# Sheet1.net
KiCad netlist of a schematic drawn in Altium Designer
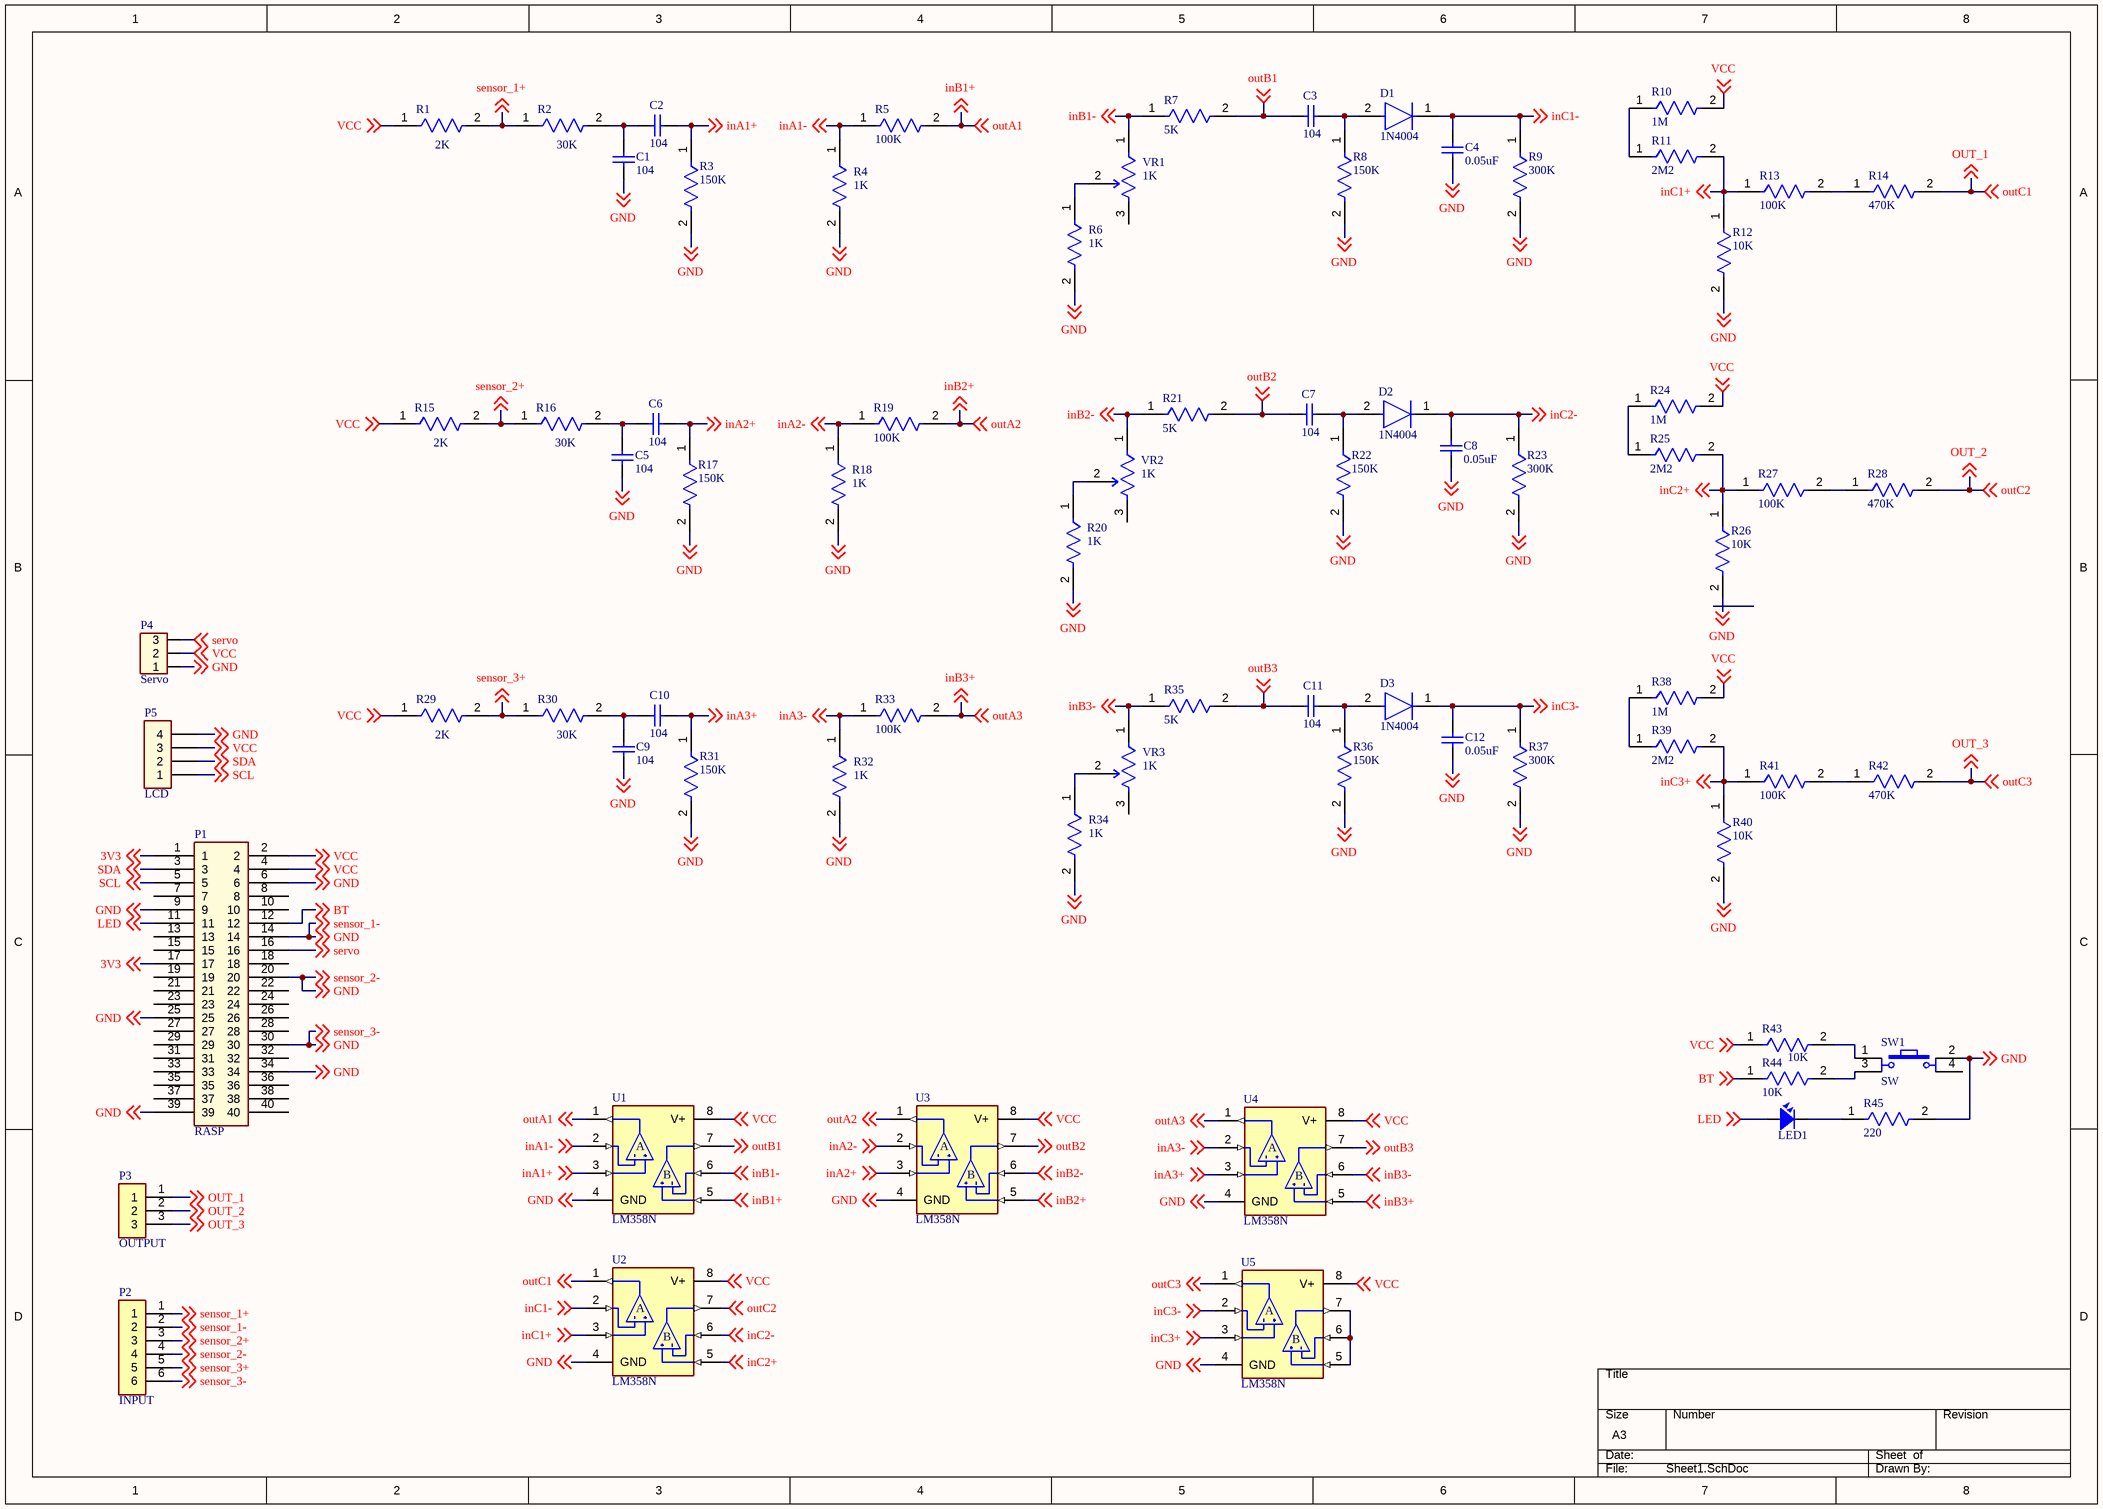
[diagram p0: Sheet1.SchDoc]

(export (version "E")
  (design (tool "Eeschema 10.0.6"))
  (components
    (comp (ref "C1")
      (value "104")
      (footprint "CAP_CERAMIC_MULTI")
      (description "Radial Multilayer Ceramic Capacitor")
      (fields
        (field (name "MANUFACTURER") "Kyocera AVX")
        (field (name "MANUFACTURER PART NUMBER") "LD051C104KAB2A")
      )
      (libsource (lib "Lib_BookTS") (part "CAP RADIAL"))
    )
    (comp (ref "C2")
      (value "104")
      (footprint "CAP_CERAMIC_MULTI")
      (description "Radial Multilayer Ceramic Capacitor")
      (fields
        (field (name "MANUFACTURER") "Kyocera AVX")
        (field (name "MANUFACTURER PART NUMBER") "LD051C104KAB2A")
      )
      (libsource (lib "Lib_BookTS") (part "CAP RADIAL"))
    )
    (comp (ref "C3")
      (value "104")
      (footprint "CAP_CERAMIC_MULTI")
      (description "Radial Multilayer Ceramic Capacitor")
      (fields
        (field (name "MANUFACTURER") "Kyocera AVX")
        (field (name "MANUFACTURER PART NUMBER") "LD051C104KAB2A")
      )
      (libsource (lib "Lib_BookTS") (part "CAP RADIAL"))
    )
    (comp (ref "C4")
      (value "0.05uF")
      (footprint "CAP_CERAMIC_MULTI")
      (description "Radial Multilayer Ceramic Capacitor")
      (fields
        (field (name "MANUFACTURER") "Kyocera AVX")
        (field (name "MANUFACTURER PART NUMBER") "LD051C104KAB2A")
      )
      (libsource (lib "Lib_BookTS") (part "CAP RADIAL"))
    )
    (comp (ref "C5")
      (value "104")
      (footprint "CAP_CERAMIC_MULTI")
      (description "Radial Multilayer Ceramic Capacitor")
      (fields
        (field (name "MANUFACTURER") "Kyocera AVX")
        (field (name "MANUFACTURER PART NUMBER") "LD051C104KAB2A")
      )
      (libsource (lib "Lib_BookTS") (part "CAP RADIAL"))
    )
    (comp (ref "C6")
      (value "104")
      (footprint "CAP_CERAMIC_MULTI")
      (description "Radial Multilayer Ceramic Capacitor")
      (fields
        (field (name "MANUFACTURER") "Kyocera AVX")
        (field (name "MANUFACTURER PART NUMBER") "LD051C104KAB2A")
      )
      (libsource (lib "Lib_BookTS") (part "CAP RADIAL"))
    )
    (comp (ref "C7")
      (value "104")
      (footprint "CAP_CERAMIC_MULTI")
      (description "Radial Multilayer Ceramic Capacitor")
      (fields
        (field (name "MANUFACTURER") "Kyocera AVX")
        (field (name "MANUFACTURER PART NUMBER") "LD051C104KAB2A")
      )
      (libsource (lib "Lib_BookTS") (part "CAP RADIAL"))
    )
    (comp (ref "C8")
      (value "0.05uF")
      (footprint "CAP_CERAMIC_MULTI")
      (description "Radial Multilayer Ceramic Capacitor")
      (fields
        (field (name "MANUFACTURER") "Kyocera AVX")
        (field (name "MANUFACTURER PART NUMBER") "LD051C104KAB2A")
      )
      (libsource (lib "Lib_BookTS") (part "CAP RADIAL"))
    )
    (comp (ref "C9")
      (value "104")
      (footprint "CAP_CERAMIC_MULTI")
      (description "Radial Multilayer Ceramic Capacitor")
      (fields
        (field (name "MANUFACTURER") "Kyocera AVX")
        (field (name "MANUFACTURER PART NUMBER") "LD051C104KAB2A")
      )
      (libsource (lib "Lib_BookTS") (part "CAP RADIAL"))
    )
    (comp (ref "C10")
      (value "104")
      (footprint "CAP_CERAMIC_MULTI")
      (description "Radial Multilayer Ceramic Capacitor")
      (fields
        (field (name "MANUFACTURER") "Kyocera AVX")
        (field (name "MANUFACTURER PART NUMBER") "LD051C104KAB2A")
      )
      (libsource (lib "Lib_BookTS") (part "CAP RADIAL"))
    )
    (comp (ref "C11")
      (value "104")
      (footprint "CAP_CERAMIC_MULTI")
      (description "Radial Multilayer Ceramic Capacitor")
      (fields
        (field (name "MANUFACTURER") "Kyocera AVX")
        (field (name "MANUFACTURER PART NUMBER") "LD051C104KAB2A")
      )
      (libsource (lib "Lib_BookTS") (part "CAP RADIAL"))
    )
    (comp (ref "C12")
      (value "0.05uF")
      (footprint "CAP_CERAMIC_MULTI")
      (description "Radial Multilayer Ceramic Capacitor")
      (fields
        (field (name "MANUFACTURER") "Kyocera AVX")
        (field (name "MANUFACTURER PART NUMBER") "LD051C104KAB2A")
      )
      (libsource (lib "Lib_BookTS") (part "CAP RADIAL"))
    )
    (comp (ref "D1")
      (value "1N4004")
      (footprint "DO-41")
      (description "Diode 1N4004 DO-41, 400V, 1.00A")
      (fields (field (name "MANUFACTURER") "Diotec") (field (name "MANUFACTURER PART NUMBER") "1N4007"))
      (libsource (lib "Lib_BookTS") (part "1N4004"))
    )
    (comp (ref "D2")
      (value "1N4004")
      (footprint "DO-41")
      (description "Diode 1N4004 DO-41, 400V, 1.00A")
      (fields (field (name "MANUFACTURER") "Diotec") (field (name "MANUFACTURER PART NUMBER") "1N4007"))
      (libsource (lib "Lib_BookTS") (part "1N4004"))
    )
    (comp (ref "D3")
      (value "1N4004")
      (footprint "DO-41")
      (description "Diode 1N4004 DO-41, 400V, 1.00A")
      (fields (field (name "MANUFACTURER") "Diotec") (field (name "MANUFACTURER PART NUMBER") "1N4007"))
      (libsource (lib "Lib_BookTS") (part "1N4004"))
    )
    (comp (ref "LED1")
      (value "LED")
      (footprint "LED-5-BLUE")
      (description "LED Single colour Green and Red")
      (libsource (lib "Lib_BookTS") (part "LED"))
    )
    (comp (ref "P1")
      (value "RASP")
      (footprint "HED20X2")
      (description "HEADER 2X20P")
      (fields (field (name "MANUFACTURER") "Harwin") (field (name "MANUFACTURER PART NUMBER") "M20-9990246"))
      (libsource (lib "Lib_BookTS") (part "HEADER 2X20P"))
    )
    (comp (ref "P2")
      (value "INPUT")
      (footprint "JP6")
      (fields (field (name "MANUFACTURER") "Harwin") (field (name "MANUFACTURER PART NUMBER") "M20-9990246"))
      (libsource (lib "Lib_BookTS") (part "JP6"))
    )
    (comp (ref "P3")
      (value "OUTPUT")
      (footprint "JP3")
      (description "HEADER 3P")
      (fields (field (name "MANUFACTURER") "Harwin") (field (name "MANUFACTURER PART NUMBER") "M20-9990246"))
      (libsource (lib "Lib_BookTS") (part "JP3"))
    )
    (comp (ref "P4")
      (value "Servo")
      (footprint "CON3")
      (description "Connector 3")
      (libsource (lib "Lib_BookTS") (part "Con3"))
    )
    (comp (ref "P5")
      (value "LCD")
      (footprint "CON4")
      (description "Connector 4")
      (libsource (lib "Lib_BookTS") (part "CON 4"))
    )
    (comp (ref "R1")
      (value "2K")
      (footprint "RES-1/8W-SMALL")
      (description "RES 1/8W")
      (fields
        (field (name "MANUFACTURER") "Bourns")
        (field (name "MANUFACTURER PART NUMBER") "CR0805-JW-331ELF")
      )
      (libsource (lib "Lib_BookTS") (part "RES-1/8W"))
    )
    (comp (ref "R2")
      (value "30K")
      (footprint "RES-1/8W-SMALL")
      (description "RES 1/8W")
      (fields
        (field (name "MANUFACTURER") "Bourns")
        (field (name "MANUFACTURER PART NUMBER") "CR0805-JW-331ELF")
      )
      (libsource (lib "Lib_BookTS") (part "RES-1/8W"))
    )
    (comp (ref "R3")
      (value "150K")
      (footprint "RES-1/8W-SMALL")
      (description "RES 1/8W")
      (fields
        (field (name "MANUFACTURER") "Bourns")
        (field (name "MANUFACTURER PART NUMBER") "CR0805-JW-331ELF")
      )
      (libsource (lib "Lib_BookTS") (part "RES-1/8W"))
    )
    (comp (ref "R4")
      (value "1K")
      (footprint "RES-1/8W-SMALL")
      (description "RES 1/8W")
      (fields
        (field (name "MANUFACTURER") "Bourns")
        (field (name "MANUFACTURER PART NUMBER") "CR0805-JW-331ELF")
      )
      (libsource (lib "Lib_BookTS") (part "RES-1/8W"))
    )
    (comp (ref "R5")
      (value "100K")
      (footprint "RES-1/8W-SMALL")
      (description "RES 1/8W")
      (fields
        (field (name "MANUFACTURER") "Bourns")
        (field (name "MANUFACTURER PART NUMBER") "CR0805-JW-331ELF")
      )
      (libsource (lib "Lib_BookTS") (part "RES-1/8W"))
    )
    (comp (ref "R6")
      (value "1K")
      (footprint "RES-1/8W-SMALL")
      (description "RES 1/8W")
      (fields
        (field (name "MANUFACTURER") "Bourns")
        (field (name "MANUFACTURER PART NUMBER") "CR0805-JW-331ELF")
      )
      (libsource (lib "Lib_BookTS") (part "RES-1/8W"))
    )
    (comp (ref "R7")
      (value "5K")
      (footprint "RES-1/8W-SMALL")
      (description "RES 1/8W")
      (fields
        (field (name "MANUFACTURER") "Bourns")
        (field (name "MANUFACTURER PART NUMBER") "CR0805-JW-331ELF")
      )
      (libsource (lib "Lib_BookTS") (part "RES-1/8W"))
    )
    (comp (ref "R8")
      (value "150K")
      (footprint "RES-1/8W-SMALL")
      (description "RES 1/8W")
      (fields
        (field (name "MANUFACTURER") "Bourns")
        (field (name "MANUFACTURER PART NUMBER") "CR0805-JW-331ELF")
      )
      (libsource (lib "Lib_BookTS") (part "RES-1/8W"))
    )
    (comp (ref "R9")
      (value "300K")
      (footprint "RES-1/8W-SMALL")
      (description "RES 1/8W")
      (fields
        (field (name "MANUFACTURER") "Bourns")
        (field (name "MANUFACTURER PART NUMBER") "CR0805-JW-331ELF")
      )
      (libsource (lib "Lib_BookTS") (part "RES-1/8W"))
    )
    (comp (ref "R10")
      (value "1M")
      (footprint "RES-1/8W-SMALL")
      (description "RES 1/8W")
      (fields
        (field (name "MANUFACTURER") "Bourns")
        (field (name "MANUFACTURER PART NUMBER") "CR0805-JW-331ELF")
      )
      (libsource (lib "Lib_BookTS") (part "RES-1/8W"))
    )
    (comp (ref "R11")
      (value "2M2")
      (footprint "RES-1/8W-SMALL")
      (description "RES 1/8W")
      (fields
        (field (name "MANUFACTURER") "Bourns")
        (field (name "MANUFACTURER PART NUMBER") "CR0805-JW-331ELF")
      )
      (libsource (lib "Lib_BookTS") (part "RES-1/8W"))
    )
    (comp (ref "R12")
      (value "10K")
      (footprint "RES-1/8W-SMALL")
      (description "RES 1/8W")
      (fields
        (field (name "MANUFACTURER") "Bourns")
        (field (name "MANUFACTURER PART NUMBER") "CR0805-JW-331ELF")
      )
      (libsource (lib "Lib_BookTS") (part "RES-1/8W"))
    )
    (comp (ref "R13")
      (value "100K")
      (footprint "RES-1/8W-SMALL")
      (description "RES 1/8W")
      (fields
        (field (name "MANUFACTURER") "Bourns")
        (field (name "MANUFACTURER PART NUMBER") "CR0805-JW-331ELF")
      )
      (libsource (lib "Lib_BookTS") (part "RES-1/8W"))
    )
    (comp (ref "R14")
      (value "470K")
      (footprint "RES-1/8W-SMALL")
      (description "RES 1/8W")
      (fields
        (field (name "MANUFACTURER") "Bourns")
        (field (name "MANUFACTURER PART NUMBER") "CR0805-JW-331ELF")
      )
      (libsource (lib "Lib_BookTS") (part "RES-1/8W"))
    )
    (comp (ref "R15")
      (value "2K")
      (footprint "RES-1/8W-SMALL")
      (description "RES 1/8W")
      (fields
        (field (name "MANUFACTURER") "Bourns")
        (field (name "MANUFACTURER PART NUMBER") "CR0805-JW-331ELF")
      )
      (libsource (lib "Lib_BookTS") (part "RES-1/8W"))
    )
    (comp (ref "R16")
      (value "30K")
      (footprint "RES-1/8W-SMALL")
      (description "RES 1/8W")
      (fields
        (field (name "MANUFACTURER") "Bourns")
        (field (name "MANUFACTURER PART NUMBER") "CR0805-JW-331ELF")
      )
      (libsource (lib "Lib_BookTS") (part "RES-1/8W"))
    )
    (comp (ref "R17")
      (value "150K")
      (footprint "RES-1/8W-SMALL")
      (description "RES 1/8W")
      (fields
        (field (name "MANUFACTURER") "Bourns")
        (field (name "MANUFACTURER PART NUMBER") "CR0805-JW-331ELF")
      )
      (libsource (lib "Lib_BookTS") (part "RES-1/8W"))
    )
    (comp (ref "R18")
      (value "1K")
      (footprint "RES-1/8W-SMALL")
      (description "RES 1/8W")
      (fields
        (field (name "MANUFACTURER") "Bourns")
        (field (name "MANUFACTURER PART NUMBER") "CR0805-JW-331ELF")
      )
      (libsource (lib "Lib_BookTS") (part "RES-1/8W"))
    )
    (comp (ref "R19")
      (value "100K")
      (footprint "RES-1/8W-SMALL")
      (description "RES 1/8W")
      (fields
        (field (name "MANUFACTURER") "Bourns")
        (field (name "MANUFACTURER PART NUMBER") "CR0805-JW-331ELF")
      )
      (libsource (lib "Lib_BookTS") (part "RES-1/8W"))
    )
    (comp (ref "R20")
      (value "1K")
      (footprint "RES-1/8W-SMALL")
      (description "RES 1/8W")
      (fields
        (field (name "MANUFACTURER") "Bourns")
        (field (name "MANUFACTURER PART NUMBER") "CR0805-JW-331ELF")
      )
      (libsource (lib "Lib_BookTS") (part "RES-1/8W"))
    )
    (comp (ref "R21")
      (value "5K")
      (footprint "RES-1/8W-SMALL")
      (description "RES 1/8W")
      (fields
        (field (name "MANUFACTURER") "Bourns")
        (field (name "MANUFACTURER PART NUMBER") "CR0805-JW-331ELF")
      )
      (libsource (lib "Lib_BookTS") (part "RES-1/8W"))
    )
    (comp (ref "R22")
      (value "150K")
      (footprint "RES-1/8W-SMALL")
      (description "RES 1/8W")
      (fields
        (field (name "MANUFACTURER") "Bourns")
        (field (name "MANUFACTURER PART NUMBER") "CR0805-JW-331ELF")
      )
      (libsource (lib "Lib_BookTS") (part "RES-1/8W"))
    )
    (comp (ref "R23")
      (value "300K")
      (footprint "RES-1/8W-SMALL")
      (description "RES 1/8W")
      (fields
        (field (name "MANUFACTURER") "Bourns")
        (field (name "MANUFACTURER PART NUMBER") "CR0805-JW-331ELF")
      )
      (libsource (lib "Lib_BookTS") (part "RES-1/8W"))
    )
    (comp (ref "R24")
      (value "1M")
      (footprint "RES-1/8W-SMALL")
      (description "RES 1/8W")
      (fields
        (field (name "MANUFACTURER") "Bourns")
        (field (name "MANUFACTURER PART NUMBER") "CR0805-JW-331ELF")
      )
      (libsource (lib "Lib_BookTS") (part "RES-1/8W"))
    )
    (comp (ref "R25")
      (value "2M2")
      (footprint "RES-1/8W-SMALL")
      (description "RES 1/8W")
      (fields
        (field (name "MANUFACTURER") "Bourns")
        (field (name "MANUFACTURER PART NUMBER") "CR0805-JW-331ELF")
      )
      (libsource (lib "Lib_BookTS") (part "RES-1/8W"))
    )
    (comp (ref "R26")
      (value "10K")
      (footprint "RES-1/8W-SMALL")
      (description "RES 1/8W")
      (fields
        (field (name "MANUFACTURER") "Bourns")
        (field (name "MANUFACTURER PART NUMBER") "CR0805-JW-331ELF")
      )
      (libsource (lib "Lib_BookTS") (part "RES-1/8W"))
    )
    (comp (ref "R27")
      (value "100K")
      (footprint "RES-1/8W-SMALL")
      (description "RES 1/8W")
      (fields
        (field (name "MANUFACTURER") "Bourns")
        (field (name "MANUFACTURER PART NUMBER") "CR0805-JW-331ELF")
      )
      (libsource (lib "Lib_BookTS") (part "RES-1/8W"))
    )
    (comp (ref "R28")
      (value "470K")
      (footprint "RES-1/8W-SMALL")
      (description "RES 1/8W")
      (fields
        (field (name "MANUFACTURER") "Bourns")
        (field (name "MANUFACTURER PART NUMBER") "CR0805-JW-331ELF")
      )
      (libsource (lib "Lib_BookTS") (part "RES-1/8W"))
    )
    (comp (ref "R29")
      (value "2K")
      (footprint "RES-1/8W-SMALL")
      (description "RES 1/8W")
      (fields
        (field (name "MANUFACTURER") "Bourns")
        (field (name "MANUFACTURER PART NUMBER") "CR0805-JW-331ELF")
      )
      (libsource (lib "Lib_BookTS") (part "RES-1/8W"))
    )
    (comp (ref "R30")
      (value "30K")
      (footprint "RES-1/8W-SMALL")
      (description "RES 1/8W")
      (fields
        (field (name "MANUFACTURER") "Bourns")
        (field (name "MANUFACTURER PART NUMBER") "CR0805-JW-331ELF")
      )
      (libsource (lib "Lib_BookTS") (part "RES-1/8W"))
    )
    (comp (ref "R31")
      (value "150K")
      (footprint "RES-1/8W-SMALL")
      (description "RES 1/8W")
      (fields
        (field (name "MANUFACTURER") "Bourns")
        (field (name "MANUFACTURER PART NUMBER") "CR0805-JW-331ELF")
      )
      (libsource (lib "Lib_BookTS") (part "RES-1/8W"))
    )
    (comp (ref "R32")
      (value "1K")
      (footprint "RES-1/8W-SMALL")
      (description "RES 1/8W")
      (fields
        (field (name "MANUFACTURER") "Bourns")
        (field (name "MANUFACTURER PART NUMBER") "CR0805-JW-331ELF")
      )
      (libsource (lib "Lib_BookTS") (part "RES-1/8W"))
    )
    (comp (ref "R33")
      (value "100K")
      (footprint "RES-1/8W-SMALL")
      (description "RES 1/8W")
      (fields
        (field (name "MANUFACTURER") "Bourns")
        (field (name "MANUFACTURER PART NUMBER") "CR0805-JW-331ELF")
      )
      (libsource (lib "Lib_BookTS") (part "RES-1/8W"))
    )
    (comp (ref "R34")
      (value "1K")
      (footprint "RES-1/8W-SMALL")
      (description "RES 1/8W")
      (fields
        (field (name "MANUFACTURER") "Bourns")
        (field (name "MANUFACTURER PART NUMBER") "CR0805-JW-331ELF")
      )
      (libsource (lib "Lib_BookTS") (part "RES-1/8W"))
    )
    (comp (ref "R35")
      (value "5K")
      (footprint "RES-1/8W-SMALL")
      (description "RES 1/8W")
      (fields
        (field (name "MANUFACTURER") "Bourns")
        (field (name "MANUFACTURER PART NUMBER") "CR0805-JW-331ELF")
      )
      (libsource (lib "Lib_BookTS") (part "RES-1/8W"))
    )
    (comp (ref "R36")
      (value "150K")
      (footprint "RES-1/8W-SMALL")
      (description "RES 1/8W")
      (fields
        (field (name "MANUFACTURER") "Bourns")
        (field (name "MANUFACTURER PART NUMBER") "CR0805-JW-331ELF")
      )
      (libsource (lib "Lib_BookTS") (part "RES-1/8W"))
    )
    (comp (ref "R37")
      (value "300K")
      (footprint "RES-1/8W-SMALL")
      (description "RES 1/8W")
      (fields
        (field (name "MANUFACTURER") "Bourns")
        (field (name "MANUFACTURER PART NUMBER") "CR0805-JW-331ELF")
      )
      (libsource (lib "Lib_BookTS") (part "RES-1/8W"))
    )
    (comp (ref "R38")
      (value "1M")
      (footprint "RES-1/8W-SMALL")
      (description "RES 1/8W")
      (fields
        (field (name "MANUFACTURER") "Bourns")
        (field (name "MANUFACTURER PART NUMBER") "CR0805-JW-331ELF")
      )
      (libsource (lib "Lib_BookTS") (part "RES-1/8W"))
    )
    (comp (ref "R39")
      (value "2M2")
      (footprint "RES-1/8W-SMALL")
      (description "RES 1/8W")
      (fields
        (field (name "MANUFACTURER") "Bourns")
        (field (name "MANUFACTURER PART NUMBER") "CR0805-JW-331ELF")
      )
      (libsource (lib "Lib_BookTS") (part "RES-1/8W"))
    )
    (comp (ref "R40")
      (value "10K")
      (footprint "RES-1/8W-SMALL")
      (description "RES 1/8W")
      (fields
        (field (name "MANUFACTURER") "Bourns")
        (field (name "MANUFACTURER PART NUMBER") "CR0805-JW-331ELF")
      )
      (libsource (lib "Lib_BookTS") (part "RES-1/8W"))
    )
    (comp (ref "R41")
      (value "100K")
      (footprint "RES-1/8W-SMALL")
      (description "RES 1/8W")
      (fields
        (field (name "MANUFACTURER") "Bourns")
        (field (name "MANUFACTURER PART NUMBER") "CR0805-JW-331ELF")
      )
      (libsource (lib "Lib_BookTS") (part "RES-1/8W"))
    )
    (comp (ref "R42")
      (value "470K")
      (footprint "RES-1/8W-SMALL")
      (description "RES 1/8W")
      (fields
        (field (name "MANUFACTURER") "Bourns")
        (field (name "MANUFACTURER PART NUMBER") "CR0805-JW-331ELF")
      )
      (libsource (lib "Lib_BookTS") (part "RES-1/8W"))
    )
    (comp (ref "R43")
      (value "10K")
      (footprint "RES-1/8W-SMALL")
      (description "RES 1/8W")
      (fields
        (field (name "MANUFACTURER") "Bourns")
        (field (name "MANUFACTURER PART NUMBER") "CR0805-JW-331ELF")
      )
      (libsource (lib "Lib_BookTS") (part "RES-1/8W"))
    )
    (comp (ref "R44")
      (value "10K")
      (footprint "RES-1/8W-SMALL")
      (description "RES 1/8W")
      (fields
        (field (name "MANUFACTURER") "Bourns")
        (field (name "MANUFACTURER PART NUMBER") "CR0805-JW-331ELF")
      )
      (libsource (lib "Lib_BookTS") (part "RES-1/8W"))
    )
    (comp (ref "R45")
      (value "220")
      (footprint "RES-1/8W-SMALL")
      (description "RES 1/8W")
      (fields
        (field (name "MANUFACTURER") "Bourns")
        (field (name "MANUFACTURER PART NUMBER") "CR0805-JW-331ELF")
      )
      (libsource (lib "Lib_BookTS") (part "RES-1/8W"))
    )
    (comp (ref "SW1")
      (value "SW")
      (footprint "SW4")
      (description "Switch button 4 pin")
      (libsource (lib "Lib_BookTS") (part "SW4"))
    )
    (comp (ref "U1")
      (value "LM358N")
      (footprint "PDIP-8")
      (fields (field (name "MP") "LM358PE3"))
      (libsource (lib "Lib_BookTS") (part "LM358N"))
    )
    (comp (ref "U2")
      (value "LM358N")
      (footprint "PDIP-8")
      (fields (field (name "MP") "LM358PE3"))
      (libsource (lib "Lib_BookTS") (part "LM358N"))
    )
    (comp (ref "U3")
      (value "LM358N")
      (footprint "PDIP-8")
      (fields (field (name "MP") "LM358PE3"))
      (libsource (lib "Lib_BookTS") (part "LM358N"))
    )
    (comp (ref "U4")
      (value "LM358N")
      (footprint "PDIP-8")
      (fields (field (name "MP") "LM358PE3"))
      (libsource (lib "Lib_BookTS") (part "LM358N"))
    )
    (comp (ref "U5")
      (value "LM358N")
      (footprint "PDIP-8")
      (fields (field (name "MP") "LM358PE3"))
      (libsource (lib "Lib_BookTS") (part "LM358N"))
    )
    (comp (ref "VR1")
      (value "1K")
      (footprint "FP-3296W-MFG")
      (description "Trimmer 3296W, Cermet, Res 10 Kilohms. VR103")
      (fields
        (field (name "MANUFACTURER") "Bourns")
        (field (name "MANUFACTURER PART NUMBER") "3296W-1-103LF")
      )
      (libsource (lib "Lib_BookTS") (part "3296W-1-103LF"))
    )
    (comp (ref "VR2")
      (value "1K")
      (footprint "FP-3296W-MFG")
      (description "Trimmer 3296W, Cermet, Res 10 Kilohms. VR103")
      (fields
        (field (name "MANUFACTURER") "Bourns")
        (field (name "MANUFACTURER PART NUMBER") "3296W-1-103LF")
      )
      (libsource (lib "Lib_BookTS") (part "3296W-1-103LF"))
    )
    (comp (ref "VR3")
      (value "1K")
      (footprint "FP-3296W-MFG")
      (description "Trimmer 3296W, Cermet, Res 10 Kilohms. VR103")
      (fields
        (field (name "MANUFACTURER") "Bourns")
        (field (name "MANUFACTURER PART NUMBER") "3296W-1-103LF")
      )
      (libsource (lib "Lib_BookTS") (part "3296W-1-103LF"))
    )
  )
  (nets
    (net (code "1") (name "3V3") (class "Default")
      (node (ref "P1") (pin "1") (pinfunction "1_1") (pintype "passive"))
      (node (ref "P1") (pin "17") (pinfunction "17_17") (pintype "passive"))
    )
    (net (code "2") (name "BT") (class "Default")
      (node (ref "P1") (pin "12") (pinfunction "12_12") (pintype "passive"))
      (node (ref "R44") (pin "1") (pinfunction "1_1") (pintype "passive"))
    )
    (net (code "3") (name "GND") (class "Default")
      (node (ref "C1") (pin "1") (pinfunction "1_1") (pintype "passive"))
      (node (ref "C12") (pin "2") (pinfunction "2_2") (pintype "passive"))
      (node (ref "C4") (pin "2") (pinfunction "2_2") (pintype "passive"))
      (node (ref "C5") (pin "1") (pinfunction "1_1") (pintype "passive"))
      (node (ref "C8") (pin "2") (pinfunction "2_2") (pintype "passive"))
      (node (ref "C9") (pin "1") (pinfunction "1_1") (pintype "passive"))
      (node (ref "P1") (pin "14") (pinfunction "14_14") (pintype "passive"))
      (node (ref "P1") (pin "20") (pinfunction "20_20") (pintype "passive"))
      (node (ref "P1") (pin "25") (pinfunction "25_25") (pintype "passive"))
      (node (ref "P1") (pin "30") (pinfunction "30_30") (pintype "passive"))
      (node (ref "P1") (pin "34") (pinfunction "34_34") (pintype "passive"))
      (node (ref "P1") (pin "39") (pinfunction "39_39") (pintype "passive"))
      (node (ref "P1") (pin "6") (pinfunction "6_6") (pintype "passive"))
      (node (ref "P1") (pin "9") (pinfunction "9_9") (pintype "passive"))
      (node (ref "P2") (pin "2") (pinfunction "2_2") (pintype "passive"))
      (node (ref "P2") (pin "4") (pinfunction "4_4") (pintype "passive"))
      (node (ref "P2") (pin "6") (pinfunction "6_6") (pintype "passive"))
      (node (ref "P4") (pin "1") (pinfunction "1_1") (pintype "passive"))
      (node (ref "P5") (pin "4") (pinfunction "4_4") (pintype "passive"))
      (node (ref "R12") (pin "2") (pinfunction "2_2") (pintype "passive"))
      (node (ref "R17") (pin "2") (pinfunction "2_2") (pintype "passive"))
      (node (ref "R18") (pin "2") (pinfunction "2_2") (pintype "passive"))
      (node (ref "R20") (pin "2") (pinfunction "2_2") (pintype "passive"))
      (node (ref "R22") (pin "2") (pinfunction "2_2") (pintype "passive"))
      (node (ref "R23") (pin "2") (pinfunction "2_2") (pintype "passive"))
      (node (ref "R26") (pin "2") (pinfunction "2_2") (pintype "passive"))
      (node (ref "R3") (pin "2") (pinfunction "2_2") (pintype "passive"))
      (node (ref "R31") (pin "2") (pinfunction "2_2") (pintype "passive"))
      (node (ref "R32") (pin "2") (pinfunction "2_2") (pintype "passive"))
      (node (ref "R34") (pin "2") (pinfunction "2_2") (pintype "passive"))
      (node (ref "R36") (pin "2") (pinfunction "2_2") (pintype "passive"))
      (node (ref "R37") (pin "2") (pinfunction "2_2") (pintype "passive"))
      (node (ref "R4") (pin "2") (pinfunction "2_2") (pintype "passive"))
      (node (ref "R40") (pin "2") (pinfunction "2_2") (pintype "passive"))
      (node (ref "R45") (pin "2") (pinfunction "2_2") (pintype "passive"))
      (node (ref "R6") (pin "2") (pinfunction "2_2") (pintype "passive"))
      (node (ref "R8") (pin "2") (pinfunction "2_2") (pintype "passive"))
      (node (ref "R9") (pin "2") (pinfunction "2_2") (pintype "passive"))
      (node (ref "SW1") (pin "2") (pintype "passive"))
      (node (ref "U1") (pin "4") (pinfunction "GND_4") (pintype "power_in"))
      (node (ref "U2") (pin "4") (pinfunction "GND_4") (pintype "power_in"))
      (node (ref "U3") (pin "4") (pinfunction "GND_4") (pintype "power_in"))
      (node (ref "U4") (pin "4") (pinfunction "GND_4") (pintype "power_in"))
      (node (ref "U5") (pin "4") (pinfunction "GND_4") (pintype "power_in"))
    )
    (net (code "4") (name "LED") (class "Default")
      (node (ref "LED1") (pin "1") (pinfunction "1_1") (pintype "passive"))
      (node (ref "P1") (pin "11") (pinfunction "11_11") (pintype "passive"))
    )
    (net (code "5") (name "Net-(C1-Pad2)") (class "Default")
      (node (ref "C1") (pin "2") (pinfunction "2_2") (pintype "passive"))
      (node (ref "C2") (pin "2") (pinfunction "2_2") (pintype "passive"))
      (node (ref "R2") (pin "2") (pinfunction "2_2") (pintype "passive"))
    )
    (net (code "6") (name "Net-(C5-Pad2)") (class "Default")
      (node (ref "C5") (pin "2") (pinfunction "2_2") (pintype "passive"))
      (node (ref "C6") (pin "2") (pinfunction "2_2") (pintype "passive"))
      (node (ref "R16") (pin "2") (pinfunction "2_2") (pintype "passive"))
    )
    (net (code "7") (name "Net-(C10-Pad2)") (class "Default")
      (node (ref "C10") (pin "2") (pinfunction "2_2") (pintype "passive"))
      (node (ref "C9") (pin "2") (pinfunction "2_2") (pintype "passive"))
      (node (ref "R30") (pin "2") (pinfunction "2_2") (pintype "passive"))
    )
    (net (code "8") (name "Net-(D1-A)") (class "Default")
      (node (ref "C3") (pin "1") (pinfunction "1_1") (pintype "passive"))
      (node (ref "D1") (pin "2") (pinfunction "A_2") (pintype "passive"))
      (node (ref "R8") (pin "1") (pinfunction "1_1") (pintype "passive"))
    )
    (net (code "9") (name "Net-(D2-A)") (class "Default")
      (node (ref "C7") (pin "1") (pinfunction "1_1") (pintype "passive"))
      (node (ref "D2") (pin "2") (pinfunction "A_2") (pintype "passive"))
      (node (ref "R22") (pin "1") (pinfunction "1_1") (pintype "passive"))
    )
    (net (code "10") (name "Net-(D3-A)") (class "Default")
      (node (ref "C11") (pin "1") (pinfunction "1_1") (pintype "passive"))
      (node (ref "D3") (pin "2") (pinfunction "A_2") (pintype "passive"))
      (node (ref "R36") (pin "1") (pinfunction "1_1") (pintype "passive"))
    )
    (net (code "11") (name "Net-(LED1-Pad2)") (class "Default")
      (node (ref "LED1") (pin "2") (pinfunction "2_2") (pintype "passive"))
      (node (ref "R45") (pin "1") (pinfunction "1_1") (pintype "passive"))
    )
    (net (code "12") (name "Net-(R10-Pad1)") (class "Default")
      (node (ref "R10") (pin "1") (pinfunction "1_1") (pintype "passive"))
      (node (ref "R11") (pin "1") (pinfunction "1_1") (pintype "passive"))
    )
    (net (code "13") (name "Net-(R13-Pad2)") (class "Default")
      (node (ref "R13") (pin "2") (pinfunction "2_2") (pintype "passive"))
      (node (ref "R14") (pin "1") (pinfunction "1_1") (pintype "passive"))
    )
    (net (code "14") (name "Net-(R24-Pad1)") (class "Default")
      (node (ref "R24") (pin "1") (pinfunction "1_1") (pintype "passive"))
      (node (ref "R25") (pin "1") (pinfunction "1_1") (pintype "passive"))
    )
    (net (code "15") (name "Net-(R27-Pad2)") (class "Default")
      (node (ref "R27") (pin "2") (pinfunction "2_2") (pintype "passive"))
      (node (ref "R28") (pin "1") (pinfunction "1_1") (pintype "passive"))
    )
    (net (code "16") (name "Net-(R38-Pad1)") (class "Default")
      (node (ref "R38") (pin "1") (pinfunction "1_1") (pintype "passive"))
      (node (ref "R39") (pin "1") (pinfunction "1_1") (pintype "passive"))
    )
    (net (code "17") (name "Net-(R41-Pad2)") (class "Default")
      (node (ref "R41") (pin "2") (pinfunction "2_2") (pintype "passive"))
      (node (ref "R42") (pin "1") (pinfunction "1_1") (pintype "passive"))
    )
    (net (code "18") (name "Net-(R43-Pad2)") (class "Default")
      (node (ref "R43") (pin "2") (pinfunction "2_2") (pintype "passive"))
      (node (ref "SW1") (pin "1") (pintype "passive"))
    )
    (net (code "19") (name "Net-(R44-Pad2)") (class "Default")
      (node (ref "R44") (pin "2") (pinfunction "2_2") (pintype "passive"))
      (node (ref "SW1") (pin "3") (pintype "passive"))
    )
    (net (code "20") (name "Net-(U5-+INB)") (class "Default")
      (node (ref "U5") (pin "5") (pinfunction "+INB_5") (pintype "input"))
      (node (ref "U5") (pin "6") (pinfunction "-INB_6") (pintype "input"))
      (node (ref "U5") (pin "7") (pinfunction "OUTB_7") (pintype "output"))
    )
    (net (code "21") (name "Net-(VR1-WIPER)") (class "Default")
      (node (ref "R6") (pin "1") (pinfunction "1_1") (pintype "passive"))
      (node (ref "VR1") (pin "2") (pinfunction "WIPER_2") (pintype "passive"))
    )
    (net (code "22") (name "Net-(VR2-WIPER)") (class "Default")
      (node (ref "R20") (pin "1") (pinfunction "1_1") (pintype "passive"))
      (node (ref "VR2") (pin "2") (pinfunction "WIPER_2") (pintype "passive"))
    )
    (net (code "23") (name "Net-(VR3-WIPER)") (class "Default")
      (node (ref "R34") (pin "1") (pinfunction "1_1") (pintype "passive"))
      (node (ref "VR3") (pin "2") (pinfunction "WIPER_2") (pintype "passive"))
    )
    (net (code "24") (name "OUT_1") (class "Default")
      (node (ref "P3") (pin "1") (pinfunction "1_1") (pintype "passive"))
      (node (ref "R14") (pin "2") (pinfunction "2_2") (pintype "passive"))
      (node (ref "U2") (pin "1") (pinfunction "OUTA_1") (pintype "output"))
    )
    (net (code "25") (name "OUT_2") (class "Default")
      (node (ref "P3") (pin "2") (pinfunction "2_2") (pintype "passive"))
      (node (ref "R28") (pin "2") (pinfunction "2_2") (pintype "passive"))
      (node (ref "U2") (pin "7") (pinfunction "OUTB_7") (pintype "output"))
    )
    (net (code "26") (name "OUT_3") (class "Default")
      (node (ref "P3") (pin "3") (pinfunction "3_3") (pintype "passive"))
      (node (ref "R42") (pin "2") (pinfunction "2_2") (pintype "passive"))
      (node (ref "U5") (pin "1") (pinfunction "OUTA_1") (pintype "output"))
    )
    (net (code "27") (name "SCL") (class "Default")
      (node (ref "P1") (pin "5") (pinfunction "5_5") (pintype "passive"))
      (node (ref "P5") (pin "1") (pinfunction "1_1") (pintype "passive"))
    )
    (net (code "28") (name "SDA") (class "Default")
      (node (ref "P1") (pin "3") (pinfunction "3_3") (pintype "passive"))
      (node (ref "P5") (pin "2") (pinfunction "2_2") (pintype "passive"))
    )
    (net (code "29") (name "VCC") (class "Default")
      (node (ref "P1") (pin "2") (pinfunction "2_2") (pintype "passive"))
      (node (ref "P1") (pin "4") (pinfunction "4_4") (pintype "passive"))
      (node (ref "P4") (pin "2") (pinfunction "2_2") (pintype "passive"))
      (node (ref "P5") (pin "3") (pinfunction "3_3") (pintype "passive"))
      (node (ref "R1") (pin "1") (pinfunction "1_1") (pintype "passive"))
      (node (ref "R10") (pin "2") (pinfunction "2_2") (pintype "passive"))
      (node (ref "R15") (pin "1") (pinfunction "1_1") (pintype "passive"))
      (node (ref "R24") (pin "2") (pinfunction "2_2") (pintype "passive"))
      (node (ref "R29") (pin "1") (pinfunction "1_1") (pintype "passive"))
      (node (ref "R38") (pin "2") (pinfunction "2_2") (pintype "passive"))
      (node (ref "R43") (pin "1") (pinfunction "1_1") (pintype "passive"))
      (node (ref "U1") (pin "8") (pinfunction "V+_8") (pintype "power_in"))
      (node (ref "U2") (pin "8") (pinfunction "V+_8") (pintype "power_in"))
      (node (ref "U3") (pin "8") (pinfunction "V+_8") (pintype "power_in"))
      (node (ref "U4") (pin "8") (pinfunction "V+_8") (pintype "power_in"))
      (node (ref "U5") (pin "8") (pinfunction "V+_8") (pintype "power_in"))
    )
    (net (code "30") (name "inA1+") (class "Default")
      (node (ref "C2") (pin "1") (pinfunction "1_1") (pintype "passive"))
      (node (ref "R3") (pin "1") (pinfunction "1_1") (pintype "passive"))
      (node (ref "U1") (pin "3") (pinfunction "+INA_3") (pintype "input"))
    )
    (net (code "31") (name "inA1-") (class "Default")
      (node (ref "R4") (pin "1") (pinfunction "1_1") (pintype "passive"))
      (node (ref "R5") (pin "1") (pinfunction "1_1") (pintype "passive"))
      (node (ref "U1") (pin "2") (pinfunction "-INA_2") (pintype "input"))
    )
    (net (code "32") (name "inA2+") (class "Default")
      (node (ref "C6") (pin "1") (pinfunction "1_1") (pintype "passive"))
      (node (ref "R17") (pin "1") (pinfunction "1_1") (pintype "passive"))
      (node (ref "U3") (pin "3") (pinfunction "+INA_3") (pintype "input"))
    )
    (net (code "33") (name "inA2-") (class "Default")
      (node (ref "R18") (pin "1") (pinfunction "1_1") (pintype "passive"))
      (node (ref "R19") (pin "1") (pinfunction "1_1") (pintype "passive"))
      (node (ref "U3") (pin "2") (pinfunction "-INA_2") (pintype "input"))
    )
    (net (code "34") (name "inA3+") (class "Default")
      (node (ref "C10") (pin "1") (pinfunction "1_1") (pintype "passive"))
      (node (ref "R31") (pin "1") (pinfunction "1_1") (pintype "passive"))
      (node (ref "U4") (pin "3") (pinfunction "+INA_3") (pintype "input"))
    )
    (net (code "35") (name "inA3-") (class "Default")
      (node (ref "R32") (pin "1") (pinfunction "1_1") (pintype "passive"))
      (node (ref "R33") (pin "1") (pinfunction "1_1") (pintype "passive"))
      (node (ref "U4") (pin "2") (pinfunction "-INA_2") (pintype "input"))
    )
    (net (code "36") (name "inB1+") (class "Default")
      (node (ref "R5") (pin "2") (pinfunction "2_2") (pintype "passive"))
      (node (ref "U1") (pin "1") (pinfunction "OUTA_1") (pintype "output"))
      (node (ref "U1") (pin "5") (pinfunction "+INB_5") (pintype "input"))
    )
    (net (code "37") (name "inB1-") (class "Default")
      (node (ref "R7") (pin "1") (pinfunction "1_1") (pintype "passive"))
      (node (ref "U1") (pin "6") (pinfunction "-INB_6") (pintype "input"))
      (node (ref "VR1") (pin "1") (pinfunction "CCW_1") (pintype "passive"))
    )
    (net (code "38") (name "inB2+") (class "Default")
      (node (ref "R19") (pin "2") (pinfunction "2_2") (pintype "passive"))
      (node (ref "U3") (pin "1") (pinfunction "OUTA_1") (pintype "output"))
      (node (ref "U3") (pin "5") (pinfunction "+INB_5") (pintype "input"))
    )
    (net (code "39") (name "inB2-") (class "Default")
      (node (ref "R21") (pin "1") (pinfunction "1_1") (pintype "passive"))
      (node (ref "U3") (pin "6") (pinfunction "-INB_6") (pintype "input"))
      (node (ref "VR2") (pin "1") (pinfunction "CCW_1") (pintype "passive"))
    )
    (net (code "40") (name "inB3+") (class "Default")
      (node (ref "R33") (pin "2") (pinfunction "2_2") (pintype "passive"))
      (node (ref "U4") (pin "1") (pinfunction "OUTA_1") (pintype "output"))
      (node (ref "U4") (pin "5") (pinfunction "+INB_5") (pintype "input"))
    )
    (net (code "41") (name "inB3-") (class "Default")
      (node (ref "R35") (pin "1") (pinfunction "1_1") (pintype "passive"))
      (node (ref "U4") (pin "6") (pinfunction "-INB_6") (pintype "input"))
      (node (ref "VR3") (pin "1") (pinfunction "CCW_1") (pintype "passive"))
    )
    (net (code "42") (name "inC1+") (class "Default")
      (node (ref "R11") (pin "2") (pinfunction "2_2") (pintype "passive"))
      (node (ref "R12") (pin "1") (pinfunction "1_1") (pintype "passive"))
      (node (ref "R13") (pin "1") (pinfunction "1_1") (pintype "passive"))
      (node (ref "U2") (pin "3") (pinfunction "+INA_3") (pintype "input"))
    )
    (net (code "43") (name "inC1-") (class "Default")
      (node (ref "C4") (pin "1") (pinfunction "1_1") (pintype "passive"))
      (node (ref "D1") (pin "1") (pinfunction "C_1") (pintype "passive"))
      (node (ref "R9") (pin "1") (pinfunction "1_1") (pintype "passive"))
      (node (ref "U2") (pin "2") (pinfunction "-INA_2") (pintype "input"))
    )
    (net (code "44") (name "inC2+") (class "Default")
      (node (ref "R25") (pin "2") (pinfunction "2_2") (pintype "passive"))
      (node (ref "R26") (pin "1") (pinfunction "1_1") (pintype "passive"))
      (node (ref "R27") (pin "1") (pinfunction "1_1") (pintype "passive"))
      (node (ref "U2") (pin "5") (pinfunction "+INB_5") (pintype "input"))
    )
    (net (code "45") (name "inC2-") (class "Default")
      (node (ref "C8") (pin "1") (pinfunction "1_1") (pintype "passive"))
      (node (ref "D2") (pin "1") (pinfunction "C_1") (pintype "passive"))
      (node (ref "R23") (pin "1") (pinfunction "1_1") (pintype "passive"))
      (node (ref "U2") (pin "6") (pinfunction "-INB_6") (pintype "input"))
    )
    (net (code "46") (name "inC3+") (class "Default")
      (node (ref "R39") (pin "2") (pinfunction "2_2") (pintype "passive"))
      (node (ref "R40") (pin "1") (pinfunction "1_1") (pintype "passive"))
      (node (ref "R41") (pin "1") (pinfunction "1_1") (pintype "passive"))
      (node (ref "U5") (pin "3") (pinfunction "+INA_3") (pintype "input"))
    )
    (net (code "47") (name "inC3-") (class "Default")
      (node (ref "C12") (pin "1") (pinfunction "1_1") (pintype "passive"))
      (node (ref "D3") (pin "1") (pinfunction "C_1") (pintype "passive"))
      (node (ref "R37") (pin "1") (pinfunction "1_1") (pintype "passive"))
      (node (ref "U5") (pin "2") (pinfunction "-INA_2") (pintype "input"))
    )
    (net (code "48") (name "outB1") (class "Default")
      (node (ref "C3") (pin "2") (pinfunction "2_2") (pintype "passive"))
      (node (ref "R7") (pin "2") (pinfunction "2_2") (pintype "passive"))
      (node (ref "U1") (pin "7") (pinfunction "OUTB_7") (pintype "output"))
    )
    (net (code "49") (name "outB2") (class "Default")
      (node (ref "C7") (pin "2") (pinfunction "2_2") (pintype "passive"))
      (node (ref "R21") (pin "2") (pinfunction "2_2") (pintype "passive"))
      (node (ref "U3") (pin "7") (pinfunction "OUTB_7") (pintype "output"))
    )
    (net (code "50") (name "outB3") (class "Default")
      (node (ref "C11") (pin "2") (pinfunction "2_2") (pintype "passive"))
      (node (ref "R35") (pin "2") (pinfunction "2_2") (pintype "passive"))
      (node (ref "U4") (pin "7") (pinfunction "OUTB_7") (pintype "output"))
    )
    (net (code "51") (name "sensor_1+") (class "Default")
      (node (ref "P2") (pin "1") (pinfunction "1_1") (pintype "passive"))
      (node (ref "R1") (pin "2") (pinfunction "2_2") (pintype "passive"))
      (node (ref "R2") (pin "1") (pinfunction "1_1") (pintype "passive"))
    )
    (net (code "52") (name "sensor_2+") (class "Default")
      (node (ref "P2") (pin "3") (pinfunction "3_3") (pintype "passive"))
      (node (ref "R15") (pin "2") (pinfunction "2_2") (pintype "passive"))
      (node (ref "R16") (pin "1") (pinfunction "1_1") (pintype "passive"))
    )
    (net (code "53") (name "sensor_3+") (class "Default")
      (node (ref "P2") (pin "5") (pinfunction "5_5") (pintype "passive"))
      (node (ref "R29") (pin "2") (pinfunction "2_2") (pintype "passive"))
      (node (ref "R30") (pin "1") (pinfunction "1_1") (pintype "passive"))
    )
    (net (code "54") (name "servo") (class "Default")
      (node (ref "P1") (pin "16") (pinfunction "16_16") (pintype "passive"))
      (node (ref "P4") (pin "3") (pinfunction "3_3") (pintype "passive"))
    )
    (net (code "55") (name "unconnected-(P1-Pad7)") (class "Default")
      (node (ref "P1") (pin "7") (pinfunction "7_7") (pintype "passive"))
    )
    (net (code "56") (name "unconnected-(P1-Pad8)") (class "Default")
      (node (ref "P1") (pin "8") (pinfunction "8_8") (pintype "passive"))
    )
    (net (code "57") (name "unconnected-(P1-Pad10)") (class "Default")
      (node (ref "P1") (pin "10") (pinfunction "10_10") (pintype "passive"))
    )
    (net (code "58") (name "unconnected-(P1-Pad13)") (class "Default")
      (node (ref "P1") (pin "13") (pinfunction "13_13") (pintype "passive"))
    )
    (net (code "59") (name "unconnected-(P1-Pad15)") (class "Default")
      (node (ref "P1") (pin "15") (pinfunction "15_15") (pintype "passive"))
    )
    (net (code "60") (name "unconnected-(P1-Pad18)") (class "Default")
      (node (ref "P1") (pin "18") (pinfunction "18_18") (pintype "passive"))
    )
    (net (code "61") (name "unconnected-(P1-Pad19)") (class "Default")
      (node (ref "P1") (pin "19") (pinfunction "19_19") (pintype "passive"))
    )
    (net (code "62") (name "unconnected-(P1-Pad21)") (class "Default")
      (node (ref "P1") (pin "21") (pinfunction "21_21") (pintype "passive"))
    )
    (net (code "63") (name "unconnected-(P1-Pad22)") (class "Default")
      (node (ref "P1") (pin "22") (pinfunction "22_22") (pintype "passive"))
    )
    (net (code "64") (name "unconnected-(P1-Pad23)") (class "Default")
      (node (ref "P1") (pin "23") (pinfunction "23_23") (pintype "passive"))
    )
    (net (code "65") (name "unconnected-(P1-Pad24)") (class "Default")
      (node (ref "P1") (pin "24") (pinfunction "24_24") (pintype "passive"))
    )
    (net (code "66") (name "unconnected-(P1-Pad26)") (class "Default")
      (node (ref "P1") (pin "26") (pinfunction "26_26") (pintype "passive"))
    )
    (net (code "67") (name "unconnected-(P1-Pad27)") (class "Default")
      (node (ref "P1") (pin "27") (pinfunction "27_27") (pintype "passive"))
    )
    (net (code "68") (name "unconnected-(P1-Pad28)") (class "Default")
      (node (ref "P1") (pin "28") (pinfunction "28_28") (pintype "passive"))
    )
    (net (code "69") (name "unconnected-(P1-Pad29)") (class "Default")
      (node (ref "P1") (pin "29") (pinfunction "29_29") (pintype "passive"))
    )
    (net (code "70") (name "unconnected-(P1-Pad31)") (class "Default")
      (node (ref "P1") (pin "31") (pinfunction "31_31") (pintype "passive"))
    )
    (net (code "71") (name "unconnected-(P1-Pad32)") (class "Default")
      (node (ref "P1") (pin "32") (pinfunction "32_32") (pintype "passive"))
    )
    (net (code "72") (name "unconnected-(P1-Pad33)") (class "Default")
      (node (ref "P1") (pin "33") (pinfunction "33_33") (pintype "passive"))
    )
    (net (code "73") (name "unconnected-(P1-Pad35)") (class "Default")
      (node (ref "P1") (pin "35") (pinfunction "35_35") (pintype "passive"))
    )
    (net (code "74") (name "unconnected-(P1-Pad36)") (class "Default")
      (node (ref "P1") (pin "36") (pinfunction "36_36") (pintype "passive"))
    )
    (net (code "75") (name "unconnected-(P1-Pad37)") (class "Default")
      (node (ref "P1") (pin "37") (pinfunction "37_37") (pintype "passive"))
    )
    (net (code "76") (name "unconnected-(P1-Pad38)") (class "Default")
      (node (ref "P1") (pin "38") (pinfunction "38_38") (pintype "passive"))
    )
    (net (code "77") (name "unconnected-(P1-Pad40)") (class "Default")
      (node (ref "P1") (pin "40") (pinfunction "40_40") (pintype "passive"))
    )
    (net (code "78") (name "unconnected-(SW1-Pad4)") (class "Default")
      (node (ref "SW1") (pin "4") (pintype "passive"))
    )
    (net (code "79") (name "unconnected-(VR1-CW-Pad3)") (class "Default")
      (node (ref "VR1") (pin "3") (pinfunction "CW_3") (pintype "passive"))
    )
    (net (code "80") (name "unconnected-(VR2-CW-Pad3)") (class "Default")
      (node (ref "VR2") (pin "3") (pinfunction "CW_3") (pintype "passive"))
    )
    (net (code "81") (name "unconnected-(VR3-CW-Pad3)") (class "Default")
      (node (ref "VR3") (pin "3") (pinfunction "CW_3") (pintype "passive"))
    )
  )
)
